# Encoder_ICMU150.net
KiCad netlist of a schematic drawn in Altium Designer
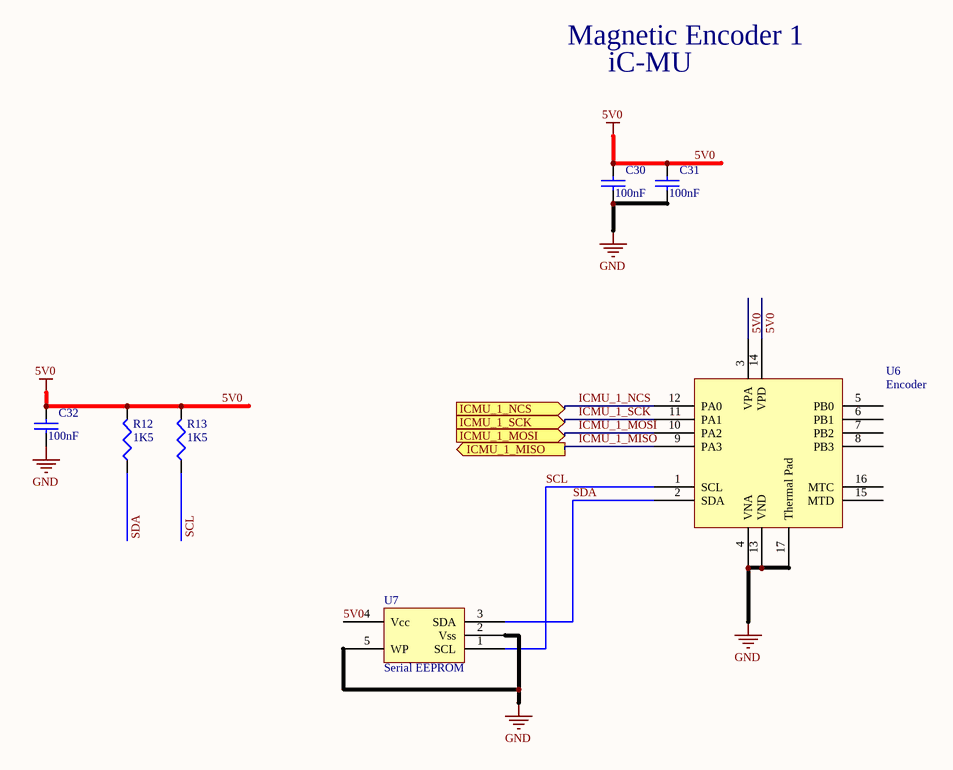
[diagram p0: Encoder_ICMU150.SchDoc]

(export (version "E")
  (design (tool "Eeschema 10.0.6"))
  (components
    (comp (ref "C30")
      (value "100nF")
      (footprint "CAP0402")
      (description "Capacitor")
      (fields
        (field (name "MANUFACTURER") "TDK Corporation")
        (field (name "MANUFACTURER PART NUMBER") "CGA2B3X7R1V104K050BB")
      )
      (libsource (lib "BPL-ShematicLibrary") (part "Capacitor"))
    )
    (comp (ref "C31")
      (value "100nF")
      (footprint "CAP0402")
      (description "Capacitor")
      (fields
        (field (name "MANUFACTURER") "TDK Corporation")
        (field (name "MANUFACTURER PART NUMBER") "CGA2B3X7R1V104K050BB")
      )
      (libsource (lib "BPL-ShematicLibrary") (part "Capacitor"))
    )
    (comp (ref "C32")
      (value "100nF")
      (footprint "CAP0402")
      (description "Capacitor")
      (fields
        (field (name "MANUFACTURER") "TDK Corporation")
        (field (name "MANUFACTURER PART NUMBER") "CGA2B3X7R1V104K050BB")
      )
      (libsource (lib "BPL-ShematicLibrary") (part "Capacitor"))
    )
    (comp (ref "R12")
      (value "1K5")
      (footprint "RES0402")
      (description "Resistor")
      (fields
        (field (name "MANUFACTURER") "Yageo")
        (field (name "MANUFACTURER PART NUMBER") "RC0402FR-071K5L")
      )
      (libsource (lib "BPL-ShematicLibrary") (part "Resistor"))
    )
    (comp (ref "R13")
      (value "1K5")
      (footprint "RES0402")
      (description "Resistor")
      (fields
        (field (name "MANUFACTURER") "Yageo")
        (field (name "MANUFACTURER PART NUMBER") "RC0402FR-071K5L")
      )
      (libsource (lib "BPL-ShematicLibrary") (part "Resistor"))
    )
    (comp (ref "U6")
      (value "Encoder")
      (footprint "iC-MU RevC2")
      (description "Off Axis Encoder with Hall Sensors")
      (fields
        (field (name "MANUFACTURER") "iC-Haus")
        (field (name "MANUFACTURER PART NUMBER") "IC-MU150DFN16-5X5")
      )
      (libsource (lib "BPL-ShematicLibrary") (part "IC-MU DFN16-5x5"))
    )
    (comp (ref "U7")
      (value "Serial EEPROM")
      (footprint "SOT23-5")
      (description "2K I2C Serial EEPROM")
      (fields
        (field (name "MANUFACTURER") "Microchip Technology")
        (field (name "MANUFACTURER PART NUMBER") "24AA02T-I/OT")
      )
      (libsource (lib "BPL-ShematicLibrary") (part "24AA02T-I/OT"))
    )
  )
  (nets
    (net (code "1") (name "/ICMU_1_MISO") (class "Default")
      (node (ref "U6") (pin "9") (pinfunction "PA3_9") (pintype "passive"))
    )
    (net (code "2") (name "/ICMU_1_MOSI") (class "Default")
      (node (ref "U6") (pin "10") (pinfunction "PA2_10") (pintype "passive"))
    )
    (net (code "3") (name "/ICMU_1_NCS") (class "Default")
      (node (ref "U6") (pin "12") (pinfunction "PA0_12") (pintype "passive"))
    )
    (net (code "4") (name "/ICMU_1_SCK") (class "Default")
      (node (ref "U6") (pin "11") (pinfunction "PA1_11") (pintype "passive"))
    )
    (net (code "5") (name "/SCL") (class "Default")
      (node (ref "R13") (pin "1") (pinfunction "1_1") (pintype "passive"))
      (node (ref "U6") (pin "1") (pinfunction "SCL_1") (pintype "passive"))
      (node (ref "U7") (pin "1") (pinfunction "SCL_1") (pintype "passive"))
    )
    (net (code "6") (name "/SDA") (class "Default")
      (node (ref "R12") (pin "1") (pinfunction "1_1") (pintype "passive"))
      (node (ref "U6") (pin "2") (pinfunction "SDA_2") (pintype "passive"))
      (node (ref "U7") (pin "3") (pinfunction "SDA_3") (pintype "passive"))
    )
    (net (code "7") (name "5V0") (class "Default")
      (node (ref "C30") (pin "1") (pinfunction "1_1") (pintype "passive"))
      (node (ref "C31") (pin "1") (pinfunction "1_1") (pintype "passive"))
      (node (ref "C32") (pin "1") (pinfunction "1_1") (pintype "passive"))
      (node (ref "R12") (pin "2") (pinfunction "2_2") (pintype "passive"))
      (node (ref "R13") (pin "2") (pinfunction "2_2") (pintype "passive"))
      (node (ref "U6") (pin "14") (pinfunction "VPD_14") (pintype "passive"))
      (node (ref "U6") (pin "3") (pinfunction "VPA_3") (pintype "passive"))
      (node (ref "U7") (pin "4") (pinfunction "Vcc_4") (pintype "passive"))
    )
    (net (code "8") (name "GND") (class "Default")
      (node (ref "C30") (pin "2") (pinfunction "2_2") (pintype "passive"))
      (node (ref "C31") (pin "2") (pinfunction "2_2") (pintype "passive"))
      (node (ref "C32") (pin "2") (pinfunction "2_2") (pintype "passive"))
      (node (ref "U6") (pin "13") (pinfunction "VND_13") (pintype "passive"))
      (node (ref "U6") (pin "17") (pinfunction "Thermal_Pad_17") (pintype "passive"))
      (node (ref "U6") (pin "4") (pinfunction "VNA_4") (pintype "passive"))
      (node (ref "U7") (pin "2") (pinfunction "Vss_2") (pintype "passive"))
      (node (ref "U7") (pin "5") (pinfunction "WP_5") (pintype "passive"))
    )
    (net (code "9") (name "unconnected-(U6-MTC-Pad16)") (class "Default")
      (node (ref "U6") (pin "16") (pinfunction "MTC_16") (pintype "passive"))
    )
    (net (code "10") (name "unconnected-(U6-MTD-Pad15)") (class "Default")
      (node (ref "U6") (pin "15") (pinfunction "MTD_15") (pintype "passive"))
    )
    (net (code "11") (name "unconnected-(U6-PB0-Pad5)") (class "Default")
      (node (ref "U6") (pin "5") (pinfunction "PB0_5") (pintype "passive"))
    )
    (net (code "12") (name "unconnected-(U6-PB1-Pad6)") (class "Default")
      (node (ref "U6") (pin "6") (pinfunction "PB1_6") (pintype "passive"))
    )
    (net (code "13") (name "unconnected-(U6-PB2-Pad7)") (class "Default")
      (node (ref "U6") (pin "7") (pinfunction "PB2_7") (pintype "passive"))
    )
    (net (code "14") (name "unconnected-(U6-PB3-Pad8)") (class "Default")
      (node (ref "U6") (pin "8") (pinfunction "PB3_8") (pintype "passive"))
    )
  )
)
